# chalupa_v3.net
KiCad netlist of a schematic drawn in EAGLE
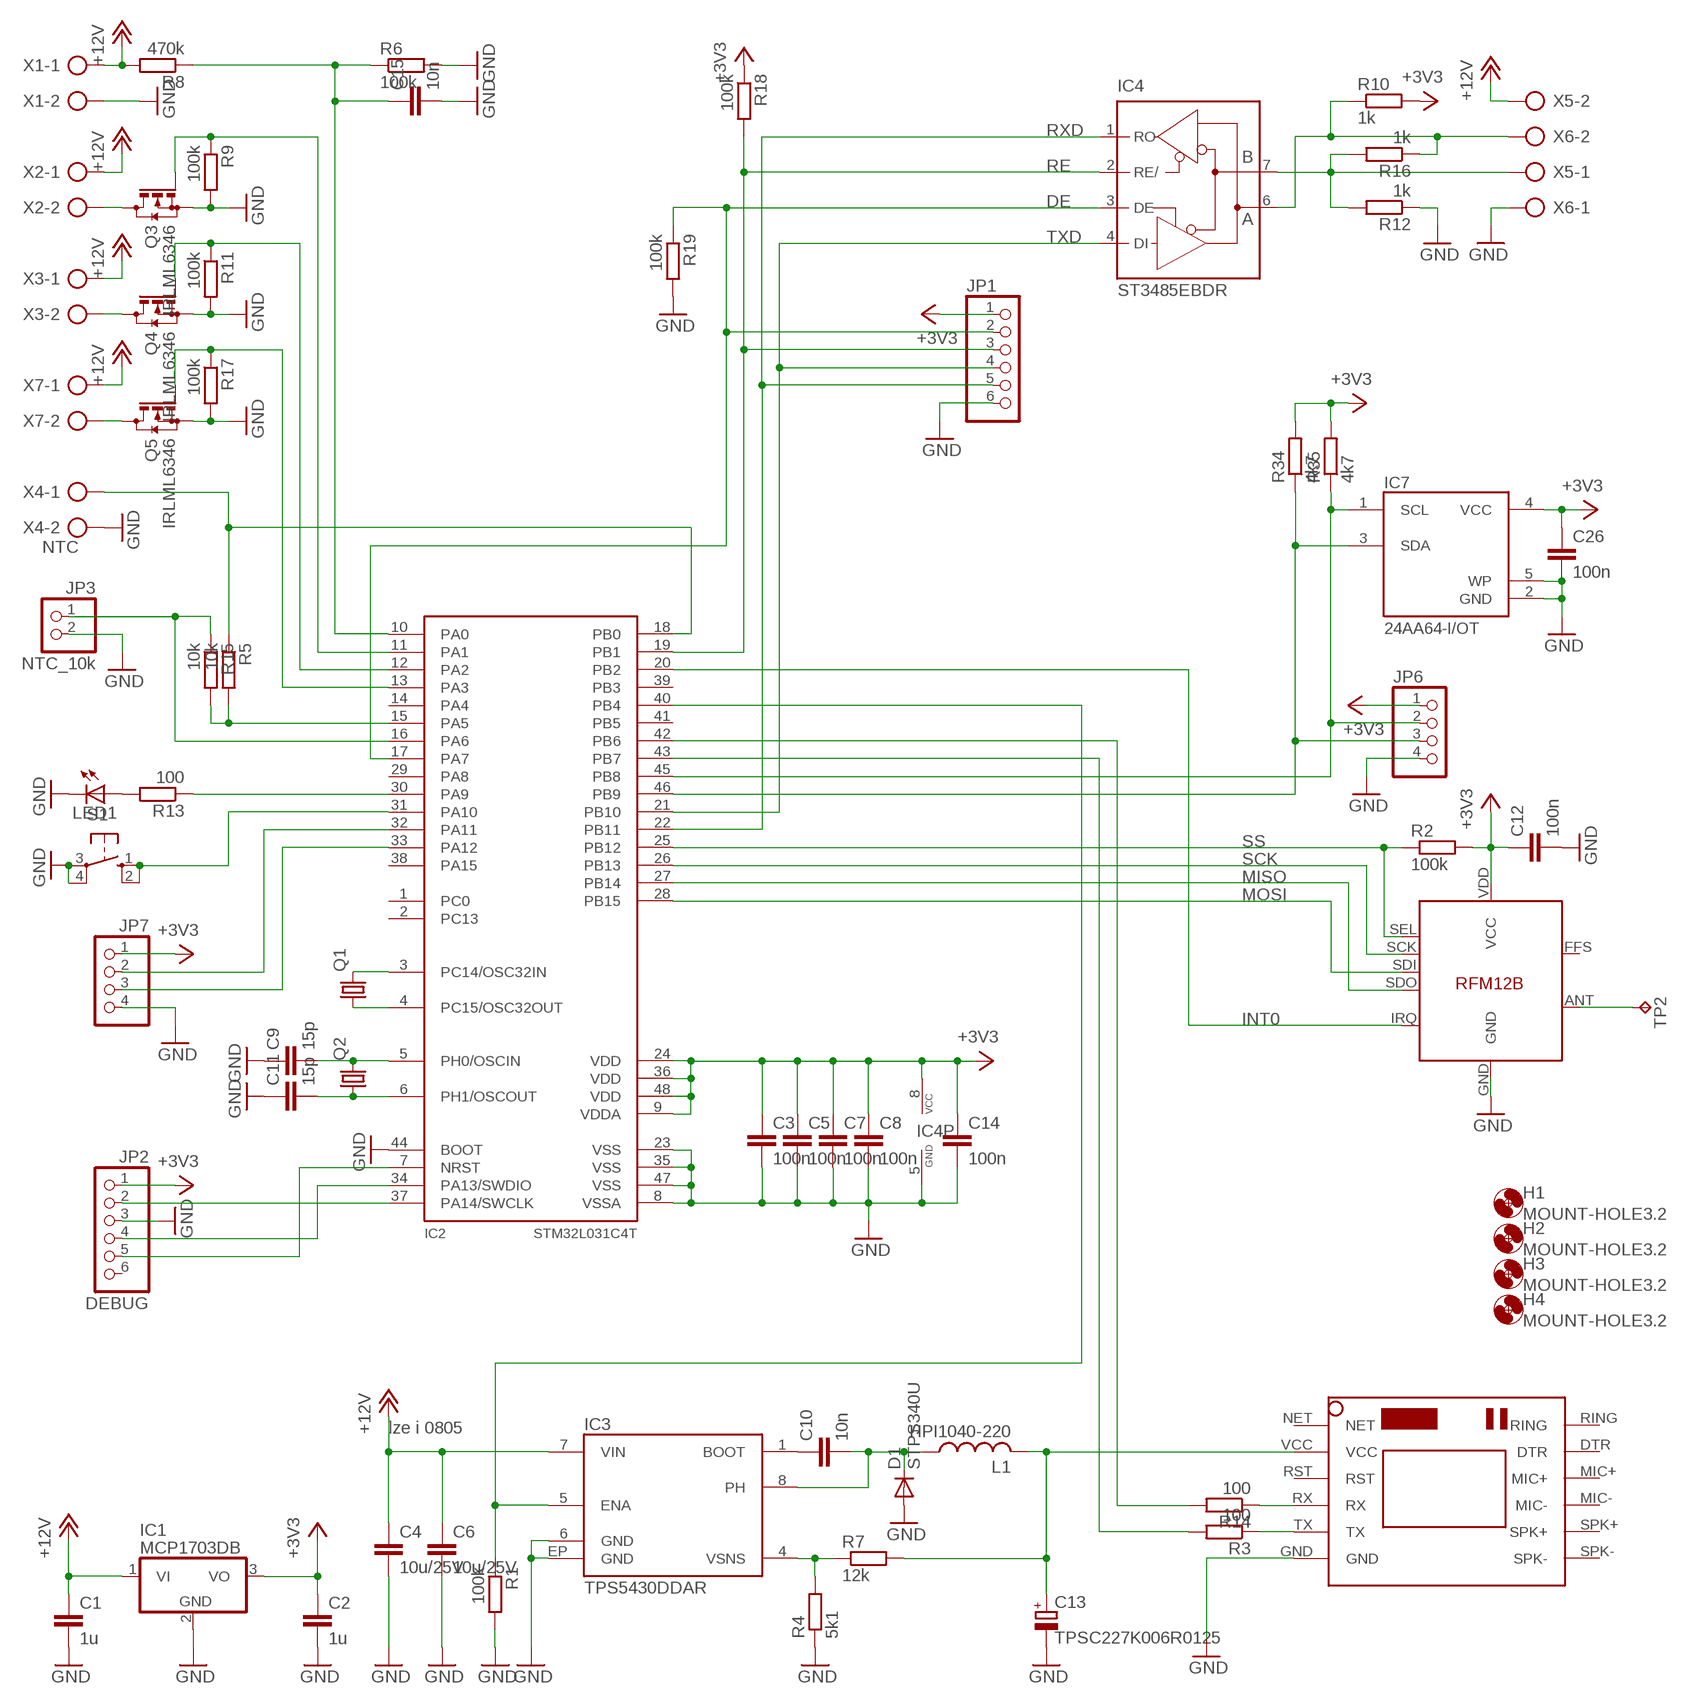
[diagram p0: schematic, sheet 1]

(export (version "E")
  (design (tool "Eeschema 10.0.6"))
  (components
    (comp (ref "C1")
      (value "1u")
      (footprint "eagle-import:C0603")
      (libsource (lib "eagle-import") (part "C-EUC0603"))
    )
    (comp (ref "C2")
      (value "1u")
      (footprint "eagle-import:C0603")
      (libsource (lib "eagle-import") (part "C-EUC0603"))
    )
    (comp (ref "C3")
      (value "100n")
      (footprint "eagle-import:C0603")
      (libsource (lib "eagle-import") (part "C-EUC0603"))
    )
    (comp (ref "C4")
      (value "10u/25V")
      (footprint "eagle-import:C1206")
      (libsource (lib "eagle-import") (part "C-EUC1206"))
    )
    (comp (ref "C5")
      (value "100n")
      (footprint "eagle-import:C0603")
      (libsource (lib "eagle-import") (part "C-EUC0603"))
    )
    (comp (ref "C6")
      (value "10u/25V")
      (footprint "eagle-import:C1206")
      (libsource (lib "eagle-import") (part "C-EUC1206"))
    )
    (comp (ref "C7")
      (value "100n")
      (footprint "eagle-import:C0603")
      (libsource (lib "eagle-import") (part "C-EUC0603"))
    )
    (comp (ref "C8")
      (value "100n")
      (footprint "eagle-import:C0603")
      (libsource (lib "eagle-import") (part "C-EUC0603"))
    )
    (comp (ref "C9")
      (value "15p")
      (footprint "eagle-import:C0603")
      (libsource (lib "eagle-import") (part "C-EUC0603"))
    )
    (comp (ref "C10")
      (value "10n")
      (footprint "eagle-import:C0603")
      (libsource (lib "eagle-import") (part "C-EUC0603"))
    )
    (comp (ref "C11")
      (value "15p")
      (footprint "eagle-import:C0603")
      (libsource (lib "eagle-import") (part "C-EUC0603"))
    )
    (comp (ref "C12")
      (value "100n")
      (footprint "eagle-import:C0603")
      (libsource (lib "eagle-import") (part "C-EUC0603"))
    )
    (comp (ref "C13")
      (value "TPSC227K006R0125")
      (footprint "eagle-import:SMC_C")
      (libsource (lib "eagle-import") (part "CPOL-EUSMCC"))
    )
    (comp (ref "C14")
      (value "100n")
      (footprint "eagle-import:C0603")
      (libsource (lib "eagle-import") (part "C-EUC0603"))
    )
    (comp (ref "C15")
      (value "10n")
      (footprint "eagle-import:C0603")
      (libsource (lib "eagle-import") (part "C-EUC0603"))
    )
    (comp (ref "C26")
      (value "100n")
      (footprint "eagle-import:C0603")
      (libsource (lib "eagle-import") (part "C-EUC0603"))
    )
    (comp (ref "D1")
      (value "STPS340U")
      (footprint "eagle-import:SMB")
      (libsource (lib "eagle-import") (part "DIODE-SMB"))
    )
    (comp (ref "H1")
      (value "MOUNT-HOLE3.2")
      (footprint "eagle-import:3,2")
      (libsource (lib "eagle-import") (part "MOUNT-HOLE3.2"))
    )
    (comp (ref "H2")
      (value "MOUNT-HOLE3.2")
      (footprint "eagle-import:3,2")
      (libsource (lib "eagle-import") (part "MOUNT-HOLE3.2"))
    )
    (comp (ref "H3")
      (value "MOUNT-HOLE3.2")
      (footprint "eagle-import:3,2")
      (libsource (lib "eagle-import") (part "MOUNT-HOLE3.2"))
    )
    (comp (ref "H4")
      (value "MOUNT-HOLE3.2")
      (footprint "eagle-import:3,2")
      (libsource (lib "eagle-import") (part "MOUNT-HOLE3.2"))
    )
    (comp (ref "IC1")
      (value "MCP1703DB")
      (footprint "eagle-import:SOT223")
      (libsource (lib "eagle-import") (part "MCP1703DB"))
    )
    (comp (ref "IC2")
      (value "STM32L031C4T")
      (footprint "eagle-import:LQFP48")
      (libsource (lib "eagle-import") (part "STM32L031C4T"))
    )
    (comp (ref "IC3")
      (value "TPS5430DDAR")
      (footprint "eagle-import:DDA")
      (libsource (lib "eagle-import") (part "TPS5430DDA"))
    )
    (comp (ref "IC4")
      (value "ST3485EBDR")
      (footprint "eagle-import:SO08")
      (fields (field (name "MF") "MAXIM") (field (name "MPN") "MAX481CSA"))
      (libsource (lib "eagle-import") (part "MAX481CSA"))
    )
    (comp (ref "IC5")
      (value "SIM800LMODULE")
      (footprint "eagle-import:SIM800LMODULE")
      (libsource (lib "eagle-import") (part "SIM800LMODULE"))
    )
    (comp (ref "IC7")
      (value "24AA64-I/OT")
      (footprint "eagle-import:SOT23-5")
      (libsource (lib "eagle-import") (part "24AA64-I/OT"))
    )
    (comp (ref "JP1")
      (value "PINHD-1X6")
      (footprint "eagle-import:1X06")
      (libsource (lib "eagle-import") (part "PINHD-1X6"))
    )
    (comp (ref "JP2")
      (value "DEBUG")
      (footprint "eagle-import:1X06")
      (libsource (lib "eagle-import") (part "PINHD-1X6"))
    )
    (comp (ref "JP3")
      (value "NTC_10k")
      (footprint "eagle-import:1X02")
      (libsource (lib "eagle-import") (part "PINHD-1X2"))
    )
    (comp (ref "JP6")
      (value "PINHD-1X4")
      (footprint "eagle-import:1X04")
      (libsource (lib "eagle-import") (part "PINHD-1X4"))
    )
    (comp (ref "JP7")
      (value "PINHD-1X4")
      (footprint "eagle-import:1X04")
      (libsource (lib "eagle-import") (part "PINHD-1X4"))
    )
    (comp (ref "L1")
      (value "HPI1040-220")
      (footprint "eagle-import:HPI1040")
      (libsource (lib "eagle-import") (part "L-USHPI1040"))
    )
    (comp (ref "LED1")
      (value "LEDCHIP-LED0805")
      (footprint "eagle-import:CHIP-LED0805")
      (libsource (lib "eagle-import") (part "LEDCHIP-LED0805"))
    )
    (comp (ref "Q1")
      (value "CRYSTALTC38H")
      (footprint "eagle-import:TC38H")
      (libsource (lib "eagle-import") (part "CRYSTALTC38H"))
    )
    (comp (ref "Q2")
      (value "CRYSTALHC49UP")
      (footprint "eagle-import:HC49UP")
      (libsource (lib "eagle-import") (part "CRYSTALHC49UP"))
    )
    (comp (ref "Q3")
      (value "IRLML6346")
      (footprint "eagle-import:SOT23")
      (libsource (lib "eagle-import") (part "BSS123"))
    )
    (comp (ref "Q4")
      (value "IRLML6346")
      (footprint "eagle-import:SOT23")
      (libsource (lib "eagle-import") (part "BSS123"))
    )
    (comp (ref "Q5")
      (value "IRLML6346")
      (footprint "eagle-import:SOT23")
      (libsource (lib "eagle-import") (part "BSS123"))
    )
    (comp (ref "R1")
      (value "100k")
      (footprint "eagle-import:R0603")
      (libsource (lib "eagle-import") (part "R-EU_R0603"))
    )
    (comp (ref "R2")
      (value "100k")
      (footprint "eagle-import:R0603")
      (libsource (lib "eagle-import") (part "R-EU_R0603"))
    )
    (comp (ref "R3")
      (value "100")
      (footprint "eagle-import:R0603")
      (libsource (lib "eagle-import") (part "R-EU_R0603"))
    )
    (comp (ref "R4")
      (value "5k1")
      (footprint "eagle-import:R0603")
      (libsource (lib "eagle-import") (part "R-EU_R0603"))
    )
    (comp (ref "R5")
      (value "10k")
      (footprint "eagle-import:R0603")
      (libsource (lib "eagle-import") (part "R-EU_R0603"))
    )
    (comp (ref "R6")
      (value "100k")
      (footprint "eagle-import:R0603")
      (libsource (lib "eagle-import") (part "R-EU_R0603"))
    )
    (comp (ref "R7")
      (value "12k")
      (footprint "eagle-import:R0603")
      (libsource (lib "eagle-import") (part "R-EU_R0603"))
    )
    (comp (ref "R8")
      (value "470k")
      (footprint "eagle-import:R0603")
      (libsource (lib "eagle-import") (part "R-EU_R0603"))
    )
    (comp (ref "R9")
      (value "100k")
      (footprint "eagle-import:R0603")
      (libsource (lib "eagle-import") (part "R-EU_R0603"))
    )
    (comp (ref "R10")
      (value "1k")
      (footprint "eagle-import:R0603")
      (libsource (lib "eagle-import") (part "R-EU_R0603"))
    )
    (comp (ref "R11")
      (value "100k")
      (footprint "eagle-import:R0603")
      (libsource (lib "eagle-import") (part "R-EU_R0603"))
    )
    (comp (ref "R12")
      (value "1k")
      (footprint "eagle-import:R0603")
      (libsource (lib "eagle-import") (part "R-EU_R0603"))
    )
    (comp (ref "R13")
      (value "100")
      (footprint "eagle-import:R0603")
      (libsource (lib "eagle-import") (part "R-EU_R0603"))
    )
    (comp (ref "R14")
      (value "100")
      (footprint "eagle-import:R0603")
      (libsource (lib "eagle-import") (part "R-EU_R0603"))
    )
    (comp (ref "R15")
      (value "10k")
      (footprint "eagle-import:R0603")
      (libsource (lib "eagle-import") (part "R-EU_R0603"))
    )
    (comp (ref "R16")
      (value "1k")
      (footprint "eagle-import:R0603")
      (libsource (lib "eagle-import") (part "R-EU_R0603"))
    )
    (comp (ref "R17")
      (value "100k")
      (footprint "eagle-import:R0603")
      (libsource (lib "eagle-import") (part "R-EU_R0603"))
    )
    (comp (ref "R18")
      (value "100k")
      (footprint "eagle-import:R0603")
      (libsource (lib "eagle-import") (part "R-EU_R0603"))
    )
    (comp (ref "R19")
      (value "100k")
      (footprint "eagle-import:R0603")
      (libsource (lib "eagle-import") (part "R-EU_R0603"))
    )
    (comp (ref "R34")
      (value "4k7")
      (footprint "eagle-import:R0603")
      (libsource (lib "eagle-import") (part "R-EU_R0603"))
    )
    (comp (ref "R35")
      (value "4k7")
      (footprint "eagle-import:R0603")
      (libsource (lib "eagle-import") (part "R-EU_R0603"))
    )
    (comp (ref "RFM12B")
      (value "RFM12B")
      (footprint "eagle-import:RFM12B")
      (libsource (lib "eagle-import") (part "RFM12B"))
    )
    (comp (ref "S1")
      (value "10-XX")
      (footprint "eagle-import:B3F-10XX")
      (fields (field (name "MPN") "B3F-1000"))
      (libsource (lib "eagle-import") (part "10-XX"))
    )
    (comp (ref "TP2")
      (value "ANT868")
      (footprint "eagle-import:B2,54")
      (libsource (lib "eagle-import") (part "TPB2,54"))
    )
    (comp (ref "X1")
      (value "AK500/2")
      (footprint "eagle-import:AK500_2")
      (libsource (lib "eagle-import") (part "AK500/2"))
    )
    (comp (ref "X2")
      (value "AK500/2")
      (footprint "eagle-import:AK500_2")
      (libsource (lib "eagle-import") (part "AK500/2"))
    )
    (comp (ref "X3")
      (value "AK500/2")
      (footprint "eagle-import:AK500_2")
      (libsource (lib "eagle-import") (part "AK500/2"))
    )
    (comp (ref "X4")
      (value "NTC")
      (footprint "eagle-import:AK500_2")
      (libsource (lib "eagle-import") (part "AK500/2"))
    )
    (comp (ref "X5")
      (value "AK500/2")
      (footprint "eagle-import:AK500_2")
      (libsource (lib "eagle-import") (part "AK500/2"))
    )
    (comp (ref "X6")
      (value "AK500/2")
      (footprint "eagle-import:AK500_2")
      (libsource (lib "eagle-import") (part "AK500/2"))
    )
    (comp (ref "X7")
      (value "AK500/2")
      (footprint "eagle-import:AK500_2")
      (libsource (lib "eagle-import") (part "AK500/2"))
    )
  )
  (nets
    (net (code "1") (name "+3V3") (class "Default")
      (node (ref "C12") (pin "1") (pinfunction "1_1") (pintype "passive"))
      (node (ref "C14") (pin "1") (pinfunction "1_1") (pintype "passive"))
      (node (ref "C2") (pin "1") (pinfunction "1_1") (pintype "passive"))
      (node (ref "C26") (pin "1") (pinfunction "1_1") (pintype "passive"))
      (node (ref "C3") (pin "1") (pinfunction "1_1") (pintype "passive"))
      (node (ref "C5") (pin "1") (pinfunction "1_1") (pintype "passive"))
      (node (ref "C7") (pin "1") (pinfunction "1_1") (pintype "passive"))
      (node (ref "C8") (pin "1") (pinfunction "1_1") (pintype "passive"))
      (node (ref "IC1") (pin "3") (pinfunction "VO_3") (pintype "passive"))
      (node (ref "IC2") (pin "24") (pinfunction "VDD_24") (pintype "power_in"))
      (node (ref "IC2") (pin "36") (pinfunction "VDD_36") (pintype "power_in"))
      (node (ref "IC2") (pin "48") (pinfunction "VDD_48") (pintype "power_in"))
      (node (ref "IC2") (pin "9") (pinfunction "VDDA_9") (pintype "power_in"))
      (node (ref "IC4") (pin "8") (pinfunction "VCC_8") (pintype "power_in"))
      (node (ref "IC7") (pin "4") (pinfunction "VCC_4") (pintype "power_in"))
      (node (ref "JP1") (pin "1") (pinfunction "1_1") (pintype "passive"))
      (node (ref "JP2") (pin "1") (pinfunction "1_1") (pintype "passive"))
      (node (ref "JP6") (pin "1") (pinfunction "1_1") (pintype "passive"))
      (node (ref "JP7") (pin "1") (pinfunction "1_1") (pintype "passive"))
      (node (ref "R10") (pin "2") (pinfunction "2_2") (pintype "passive"))
      (node (ref "R18") (pin "1") (pinfunction "1_1") (pintype "passive"))
      (node (ref "R2") (pin "2") (pinfunction "2_2") (pintype "passive"))
      (node (ref "R34") (pin "2") (pinfunction "2_2") (pintype "passive"))
      (node (ref "R35") (pin "2") (pinfunction "2_2") (pintype "passive"))
      (node (ref "RFM12B") (pin "VDD") (pinfunction "VCC_VDD") (pintype "power_in"))
    )
    (net (code "2") (name "+12V") (class "Default")
      (node (ref "C1") (pin "1") (pinfunction "1_1") (pintype "passive"))
      (node (ref "C4") (pin "1") (pinfunction "1_1") (pintype "passive"))
      (node (ref "C6") (pin "1") (pinfunction "1_1") (pintype "passive"))
      (node (ref "IC1") (pin "1") (pinfunction "VI_1") (pintype "input"))
      (node (ref "IC3") (pin "7") (pinfunction "VIN_7") (pintype "power_in"))
      (node (ref "R8") (pin "2") (pinfunction "2_2") (pintype "passive"))
      (node (ref "X1") (pin "1") (pinfunction "KL_1") (pintype "passive"))
      (node (ref "X2") (pin "1") (pinfunction "KL_1") (pintype "passive"))
      (node (ref "X3") (pin "1") (pinfunction "KL_1") (pintype "passive"))
      (node (ref "X5") (pin "2") (pinfunction "KL_2") (pintype "passive"))
      (node (ref "X7") (pin "1") (pinfunction "KL_1") (pintype "passive"))
    )
    (net (code "3") (name "/DE") (class "Default")
      (node (ref "IC2") (pin "17") (pinfunction "PA7_17") (pintype "bidirectional"))
      (node (ref "IC4") (pin "3") (pinfunction "DE_3") (pintype "input"))
      (node (ref "JP1") (pin "2") (pinfunction "2_2") (pintype "passive"))
      (node (ref "R19") (pin "1") (pinfunction "1_1") (pintype "passive"))
    )
    (net (code "4") (name "/INT0") (class "Default")
      (node (ref "IC2") (pin "20") (pinfunction "PB2_20") (pintype "bidirectional"))
      (node (ref "RFM12B") (pin "IRQ") (pinfunction "IRQ_IRQ") (pintype "open_collector"))
    )
    (net (code "5") (name "/MISO") (class "Default")
      (node (ref "IC2") (pin "27") (pinfunction "PB14_27") (pintype "bidirectional"))
      (node (ref "RFM12B") (pin "SDO") (pinfunction "SDO_SDO") (pintype "output"))
    )
    (net (code "6") (name "/MOSI") (class "Default")
      (node (ref "IC2") (pin "28") (pinfunction "PB15_28") (pintype "bidirectional"))
      (node (ref "RFM12B") (pin "SDI") (pinfunction "SDI_SDI") (pintype "input"))
    )
    (net (code "7") (name "/RE") (class "Default")
      (node (ref "IC2") (pin "19") (pinfunction "PB1_19") (pintype "bidirectional"))
      (node (ref "IC4") (pin "2") (pinfunction "RE/_2") (pintype "input"))
      (node (ref "JP1") (pin "3") (pinfunction "3_3") (pintype "passive"))
      (node (ref "R18") (pin "2") (pinfunction "2_2") (pintype "passive"))
    )
    (net (code "8") (name "/RXD") (class "Default")
      (node (ref "IC2") (pin "22") (pinfunction "PB11_22") (pintype "bidirectional"))
      (node (ref "IC4") (pin "1") (pinfunction "RO_1") (pintype "output"))
      (node (ref "JP1") (pin "5") (pinfunction "5_5") (pintype "passive"))
    )
    (net (code "9") (name "/SCK") (class "Default")
      (node (ref "IC2") (pin "26") (pinfunction "PB13_26") (pintype "bidirectional"))
      (node (ref "RFM12B") (pin "SCK") (pinfunction "SCK_SCK") (pintype "input"))
    )
    (net (code "10") (name "/SS") (class "Default")
      (node (ref "IC2") (pin "25") (pinfunction "PB12_25") (pintype "bidirectional"))
      (node (ref "R2") (pin "1") (pinfunction "1_1") (pintype "passive"))
      (node (ref "RFM12B") (pin "SEL") (pinfunction "SEL_SEL") (pintype "input"))
    )
    (net (code "11") (name "/TXD") (class "Default")
      (node (ref "IC2") (pin "21") (pinfunction "PB10_21") (pintype "bidirectional"))
      (node (ref "IC4") (pin "4") (pinfunction "DI_4") (pintype "input"))
      (node (ref "JP1") (pin "4") (pinfunction "4_4") (pintype "passive"))
    )
    (net (code "12") (name "GND") (class "Default")
      (node (ref "C1") (pin "2") (pinfunction "2_2") (pintype "passive"))
      (node (ref "C11") (pin "1") (pinfunction "1_1") (pintype "passive"))
      (node (ref "C12") (pin "2") (pinfunction "2_2") (pintype "passive"))
      (node (ref "C13") (pin "-") (pinfunction "-_-") (pintype "passive"))
      (node (ref "C14") (pin "2") (pinfunction "2_2") (pintype "passive"))
      (node (ref "C15") (pin "2") (pinfunction "2_2") (pintype "passive"))
      (node (ref "C2") (pin "2") (pinfunction "2_2") (pintype "passive"))
      (node (ref "C26") (pin "2") (pinfunction "2_2") (pintype "passive"))
      (node (ref "C3") (pin "2") (pinfunction "2_2") (pintype "passive"))
      (node (ref "C4") (pin "2") (pinfunction "2_2") (pintype "passive"))
      (node (ref "C5") (pin "2") (pinfunction "2_2") (pintype "passive"))
      (node (ref "C6") (pin "2") (pinfunction "2_2") (pintype "passive"))
      (node (ref "C7") (pin "2") (pinfunction "2_2") (pintype "passive"))
      (node (ref "C8") (pin "2") (pinfunction "2_2") (pintype "passive"))
      (node (ref "C9") (pin "1") (pinfunction "1_1") (pintype "passive"))
      (node (ref "D1") (pin "A") (pinfunction "A_A") (pintype "passive"))
      (node (ref "IC1") (pin "2") (pinfunction "GND_2") (pintype "passive"))
      (node (ref "IC2") (pin "23") (pinfunction "VSS_23") (pintype "power_in"))
      (node (ref "IC2") (pin "35") (pinfunction "VSS_35") (pintype "power_in"))
      (node (ref "IC2") (pin "44") (pinfunction "BOOT_44") (pintype "bidirectional"))
      (node (ref "IC2") (pin "47") (pinfunction "VSS_47") (pintype "power_in"))
      (node (ref "IC2") (pin "8") (pinfunction "VSSA_8") (pintype "power_in"))
      (node (ref "IC3") (pin "6") (pinfunction "GND_6") (pintype "power_in"))
      (node (ref "IC3") (pin "EP") (pinfunction "GND_EP") (pintype "power_in"))
      (node (ref "IC4") (pin "5") (pinfunction "GND_5") (pintype "power_in"))
      (node (ref "IC5") (pin "GND") (pinfunction "GND_GND") (pintype "bidirectional"))
      (node (ref "IC7") (pin "2") (pinfunction "GND_2") (pintype "power_in"))
      (node (ref "IC7") (pin "5") (pinfunction "WP_5") (pintype "input"))
      (node (ref "JP1") (pin "6") (pinfunction "6_6") (pintype "passive"))
      (node (ref "JP2") (pin "3") (pinfunction "3_3") (pintype "passive"))
      (node (ref "JP3") (pin "2") (pinfunction "2_2") (pintype "passive"))
      (node (ref "JP6") (pin "4") (pinfunction "4_4") (pintype "passive"))
      (node (ref "JP7") (pin "4") (pinfunction "4_4") (pintype "passive"))
      (node (ref "LED1") (pin "C") (pinfunction "C_C") (pintype "passive"))
      (node (ref "Q3") (pin "2") (pinfunction "S_2") (pintype "passive"))
      (node (ref "Q4") (pin "2") (pinfunction "S_2") (pintype "passive"))
      (node (ref "Q5") (pin "2") (pinfunction "S_2") (pintype "passive"))
      (node (ref "R1") (pin "2") (pinfunction "2_2") (pintype "passive"))
      (node (ref "R11") (pin "2") (pinfunction "2_2") (pintype "passive"))
      (node (ref "R12") (pin "1") (pinfunction "1_1") (pintype "passive"))
      (node (ref "R17") (pin "2") (pinfunction "2_2") (pintype "passive"))
      (node (ref "R19") (pin "2") (pinfunction "2_2") (pintype "passive"))
      (node (ref "R4") (pin "1") (pinfunction "1_1") (pintype "passive"))
      (node (ref "R6") (pin "2") (pinfunction "2_2") (pintype "passive"))
      (node (ref "R9") (pin "2") (pinfunction "2_2") (pintype "passive"))
      (node (ref "RFM12B") (pin "GND") (pinfunction "GND_GND") (pintype "power_in"))
      (node (ref "S1") (pin "3") (pinfunction "P_3") (pintype "passive"))
      (node (ref "S1") (pin "4") (pinfunction "P1_4") (pintype "passive"))
      (node (ref "X1") (pin "2") (pinfunction "KL_2") (pintype "passive"))
      (node (ref "X4") (pin "2") (pinfunction "KL_2") (pintype "passive"))
      (node (ref "X6") (pin "1") (pinfunction "KL_1") (pintype "passive"))
    )
    (net (code "13") (name "Net-(C13-Pad+)") (class "Default")
      (node (ref "C13") (pin "+") (pinfunction "+_+") (pintype "passive"))
      (node (ref "IC5") (pin "VCC") (pinfunction "VCC_VCC") (pintype "bidirectional"))
      (node (ref "L1") (pin "2") (pinfunction "2_2") (pintype "passive"))
      (node (ref "R7") (pin "2") (pinfunction "2_2") (pintype "passive"))
    )
    (net (code "14") (name "Net-(IC2-NRST)") (class "Default")
      (node (ref "IC2") (pin "7") (pinfunction "NRST_7") (pintype "bidirectional"))
      (node (ref "JP2") (pin "5") (pinfunction "5_5") (pintype "passive"))
    )
    (net (code "15") (name "Net-(IC2-PA0)") (class "Default")
      (node (ref "C15") (pin "1") (pinfunction "1_1") (pintype "passive"))
      (node (ref "IC2") (pin "10") (pinfunction "PA0_10") (pintype "bidirectional"))
      (node (ref "R6") (pin "1") (pinfunction "1_1") (pintype "passive"))
      (node (ref "R8") (pin "1") (pinfunction "1_1") (pintype "passive"))
    )
    (net (code "16") (name "Net-(IC2-PA1)") (class "Default")
      (node (ref "IC2") (pin "11") (pinfunction "PA1_11") (pintype "bidirectional"))
      (node (ref "Q3") (pin "1") (pinfunction "G_1") (pintype "passive"))
      (node (ref "R9") (pin "1") (pinfunction "1_1") (pintype "passive"))
    )
    (net (code "17") (name "Net-(IC2-PA2)") (class "Default")
      (node (ref "IC2") (pin "12") (pinfunction "PA2_12") (pintype "bidirectional"))
      (node (ref "Q4") (pin "1") (pinfunction "G_1") (pintype "passive"))
      (node (ref "R11") (pin "1") (pinfunction "1_1") (pintype "passive"))
    )
    (net (code "18") (name "Net-(IC2-PA3)") (class "Default")
      (node (ref "IC2") (pin "13") (pinfunction "PA3_13") (pintype "bidirectional"))
      (node (ref "Q5") (pin "1") (pinfunction "G_1") (pintype "passive"))
      (node (ref "R17") (pin "1") (pinfunction "1_1") (pintype "passive"))
    )
    (net (code "19") (name "Net-(IC2-PA5)") (class "Default")
      (node (ref "IC2") (pin "15") (pinfunction "PA5_15") (pintype "bidirectional"))
      (node (ref "R15") (pin "2") (pinfunction "2_2") (pintype "passive"))
      (node (ref "R5") (pin "2") (pinfunction "2_2") (pintype "passive"))
    )
    (net (code "20") (name "Net-(IC2-PA6)") (class "Default")
      (node (ref "IC2") (pin "16") (pinfunction "PA6_16") (pintype "bidirectional"))
      (node (ref "JP3") (pin "1") (pinfunction "1_1") (pintype "passive"))
      (node (ref "R15") (pin "1") (pinfunction "1_1") (pintype "passive"))
    )
    (net (code "21") (name "Net-(IC2-PA9)") (class "Default")
      (node (ref "IC2") (pin "30") (pinfunction "PA9_30") (pintype "bidirectional"))
      (node (ref "R13") (pin "1") (pinfunction "1_1") (pintype "passive"))
    )
    (net (code "22") (name "Net-(IC2-PA10)") (class "Default")
      (node (ref "IC2") (pin "31") (pinfunction "PA10_31") (pintype "bidirectional"))
      (node (ref "S1") (pin "1") (pinfunction "S_1") (pintype "passive"))
      (node (ref "S1") (pin "2") (pinfunction "S1_2") (pintype "passive"))
    )
    (net (code "23") (name "Net-(IC2-PA11)") (class "Default")
      (node (ref "IC2") (pin "32") (pinfunction "PA11_32") (pintype "bidirectional"))
      (node (ref "JP7") (pin "2") (pinfunction "2_2") (pintype "passive"))
    )
    (net (code "24") (name "Net-(IC2-PA12)") (class "Default")
      (node (ref "IC2") (pin "33") (pinfunction "PA12_33") (pintype "bidirectional"))
      (node (ref "JP7") (pin "3") (pinfunction "3_3") (pintype "passive"))
    )
    (net (code "25") (name "Net-(IC2-PA13{slash}SWDIO)") (class "Default")
      (node (ref "IC2") (pin "34") (pinfunction "PA13/SWDIO_34") (pintype "bidirectional"))
      (node (ref "JP2") (pin "4") (pinfunction "4_4") (pintype "passive"))
    )
    (net (code "26") (name "Net-(IC2-PA14{slash}SWCLK)") (class "Default")
      (node (ref "IC2") (pin "37") (pinfunction "PA14/SWCLK_37") (pintype "bidirectional"))
      (node (ref "JP2") (pin "2") (pinfunction "2_2") (pintype "passive"))
    )
    (net (code "27") (name "Net-(IC2-PB0)") (class "Default")
      (node (ref "IC2") (pin "18") (pinfunction "PB0_18") (pintype "bidirectional"))
      (node (ref "R5") (pin "1") (pinfunction "1_1") (pintype "passive"))
      (node (ref "X4") (pin "1") (pinfunction "KL_1") (pintype "passive"))
    )
    (net (code "28") (name "Net-(IC2-PB4)") (class "Default")
      (node (ref "IC2") (pin "40") (pinfunction "PB4_40") (pintype "bidirectional"))
      (node (ref "IC3") (pin "5") (pinfunction "ENA_5") (pintype "bidirectional"))
      (node (ref "R1") (pin "1") (pinfunction "1_1") (pintype "passive"))
    )
    (net (code "29") (name "Net-(IC2-PB6)") (class "Default")
      (node (ref "IC2") (pin "42") (pinfunction "PB6_42") (pintype "bidirectional"))
      (node (ref "R14") (pin "2") (pinfunction "2_2") (pintype "passive"))
    )
    (net (code "30") (name "Net-(IC2-PB7)") (class "Default")
      (node (ref "IC2") (pin "43") (pinfunction "PB7_43") (pintype "bidirectional"))
      (node (ref "R3") (pin "2") (pinfunction "2_2") (pintype "passive"))
    )
    (net (code "31") (name "Net-(IC2-PB8)") (class "Default")
      (node (ref "IC2") (pin "45") (pinfunction "PB8_45") (pintype "bidirectional"))
      (node (ref "IC7") (pin "1") (pinfunction "SCL_1") (pintype "input"))
      (node (ref "JP6") (pin "2") (pinfunction "2_2") (pintype "passive"))
      (node (ref "R35") (pin "1") (pinfunction "1_1") (pintype "passive"))
    )
    (net (code "32") (name "Net-(IC2-PB9)") (class "Default")
      (node (ref "IC2") (pin "46") (pinfunction "PB9_46") (pintype "bidirectional"))
      (node (ref "IC7") (pin "3") (pinfunction "SDA_3") (pintype "bidirectional"))
      (node (ref "JP6") (pin "3") (pinfunction "3_3") (pintype "passive"))
      (node (ref "R34") (pin "1") (pinfunction "1_1") (pintype "passive"))
    )
    (net (code "33") (name "Net-(IC2-PC14{slash}OSC32IN)") (class "Default")
      (node (ref "IC2") (pin "3") (pinfunction "PC14/OSC32IN_3") (pintype "passive"))
      (node (ref "Q1") (pin "2") (pinfunction "2_2") (pintype "passive"))
    )
    (net (code "34") (name "Net-(IC2-PC15{slash}OSC32OUT)") (class "Default")
      (node (ref "IC2") (pin "4") (pinfunction "PC15/OSC32OUT_4") (pintype "passive"))
      (node (ref "Q1") (pin "1") (pinfunction "1_1") (pintype "passive"))
    )
    (net (code "35") (name "Net-(IC2-PH0{slash}OSCIN)") (class "Default")
      (node (ref "C9") (pin "2") (pinfunction "2_2") (pintype "passive"))
      (node (ref "IC2") (pin "5") (pinfunction "PH0/OSCIN_5") (pintype "passive"))
      (node (ref "Q2") (pin "2") (pinfunction "2_2") (pintype "passive"))
    )
    (net (code "36") (name "Net-(IC2-PH1{slash}OSCOUT)") (class "Default")
      (node (ref "C11") (pin "2") (pinfunction "2_2") (pintype "passive"))
      (node (ref "IC2") (pin "6") (pinfunction "PH1/OSCOUT_6") (pintype "passive"))
      (node (ref "Q2") (pin "1") (pinfunction "1_1") (pintype "passive"))
    )
    (net (code "37") (name "Net-(IC3-BOOT)") (class "Default")
      (node (ref "C10") (pin "1") (pinfunction "1_1") (pintype "passive"))
      (node (ref "IC3") (pin "1") (pinfunction "BOOT_1") (pintype "passive"))
    )
    (net (code "38") (name "Net-(IC3-PH)") (class "Default")
      (node (ref "C10") (pin "2") (pinfunction "2_2") (pintype "passive"))
      (node (ref "D1") (pin "C") (pinfunction "C_C") (pintype "passive"))
      (node (ref "IC3") (pin "8") (pinfunction "PH_8") (pintype "passive"))
      (node (ref "L1") (pin "1") (pinfunction "1_1") (pintype "passive"))
    )
    (net (code "39") (name "Net-(IC3-VSNS)") (class "Default")
      (node (ref "IC3") (pin "4") (pinfunction "VSNS_4") (pintype "input"))
      (node (ref "R4") (pin "2") (pinfunction "2_2") (pintype "passive"))
      (node (ref "R7") (pin "1") (pinfunction "1_1") (pintype "passive"))
    )
    (net (code "40") (name "Net-(IC4A-A)") (class "Default")
      (node (ref "IC4") (pin "6") (pinfunction "A_6") (pintype "passive"))
      (node (ref "R10") (pin "1") (pinfunction "1_1") (pintype "passive"))
      (node (ref "R16") (pin "1") (pinfunction "1_1") (pintype "passive"))
      (node (ref "X6") (pin "2") (pinfunction "KL_2") (pintype "passive"))
    )
    (net (code "41") (name "Net-(IC4A-B)") (class "Default")
      (node (ref "IC4") (pin "7") (pinfunction "B_7") (pintype "passive"))
      (node (ref "R12") (pin "2") (pinfunction "2_2") (pintype "passive"))
      (node (ref "R16") (pin "2") (pinfunction "2_2") (pintype "passive"))
      (node (ref "X5") (pin "1") (pinfunction "KL_1") (pintype "passive"))
    )
    (net (code "42") (name "Net-(IC5-PadRX)") (class "Default")
      (node (ref "IC5") (pin "RX") (pinfunction "RX_RX") (pintype "bidirectional"))
      (node (ref "R14") (pin "1") (pinfunction "1_1") (pintype "passive"))
    )
    (net (code "43") (name "Net-(IC5-PadTX)") (class "Default")
      (node (ref "IC5") (pin "TX") (pinfunction "TX_TX") (pintype "bidirectional"))
      (node (ref "R3") (pin "1") (pinfunction "1_1") (pintype "passive"))
    )
    (net (code "44") (name "Net-(LED1-PadA)") (class "Default")
      (node (ref "LED1") (pin "A") (pinfunction "A_A") (pintype "passive"))
      (node (ref "R13") (pin "2") (pinfunction "2_2") (pintype "passive"))
    )
    (net (code "45") (name "Net-(Q3-D)") (class "Default")
      (node (ref "Q3") (pin "3") (pinfunction "D_3") (pintype "passive"))
      (node (ref "X2") (pin "2") (pinfunction "KL_2") (pintype "passive"))
    )
    (net (code "46") (name "Net-(Q4-D)") (class "Default")
      (node (ref "Q4") (pin "3") (pinfunction "D_3") (pintype "passive"))
      (node (ref "X3") (pin "2") (pinfunction "KL_2") (pintype "passive"))
    )
    (net (code "47") (name "Net-(Q5-D)") (class "Default")
      (node (ref "Q5") (pin "3") (pinfunction "D_3") (pintype "passive"))
      (node (ref "X7") (pin "2") (pinfunction "KL_2") (pintype "passive"))
    )
    (net (code "48") (name "Net-(TP2-TP)") (class "Default")
      (node (ref "RFM12B") (pin "ANT") (pinfunction "ANT_ANT") (pintype "passive"))
      (node (ref "TP2") (pin "PP") (pinfunction "TP_PP") (pintype "input"))
    )
    (net (code "49") (name "unconnected-(IC2-PA4-Pad14)") (class "Default")
      (node (ref "IC2") (pin "14") (pinfunction "PA4_14") (pintype "bidirectional"))
    )
    (net (code "50") (name "unconnected-(IC2-PA8-Pad29)") (class "Default")
      (node (ref "IC2") (pin "29") (pinfunction "PA8_29") (pintype "bidirectional"))
    )
    (net (code "51") (name "unconnected-(IC2-PA15-Pad38)") (class "Default")
      (node (ref "IC2") (pin "38") (pinfunction "PA15_38") (pintype "bidirectional"))
    )
    (net (code "52") (name "unconnected-(IC2-PB3-Pad39)") (class "Default")
      (node (ref "IC2") (pin "39") (pinfunction "PB3_39") (pintype "bidirectional"))
    )
    (net (code "53") (name "unconnected-(IC2-PB5-Pad41)") (class "Default")
      (node (ref "IC2") (pin "41") (pinfunction "PB5_41") (pintype "bidirectional"))
    )
    (net (code "54") (name "unconnected-(IC2-PC0-Pad1)") (class "Default")
      (node (ref "IC2") (pin "1") (pinfunction "PC0_1") (pintype "bidirectional"))
    )
    (net (code "55") (name "unconnected-(IC2-PC13-Pad2)") (class "Default")
      (node (ref "IC2") (pin "2") (pinfunction "PC13_2") (pintype "bidirectional"))
    )
    (net (code "56") (name "unconnected-(IC5-PadDTR)") (class "Default")
      (node (ref "IC5") (pin "DTR") (pinfunction "DTR_DTR") (pintype "bidirectional"))
    )
    (net (code "57") (name "unconnected-(IC5-PadMIC+)") (class "Default")
      (node (ref "IC5") (pin "MIC+") (pinfunction "MIC+_MIC+") (pintype "bidirectional"))
    )
    (net (code "58") (name "unconnected-(IC5-PadMIC-)") (class "Default")
      (node (ref "IC5") (pin "MIC-") (pinfunction "MIC-_MIC-") (pintype "bidirectional"))
    )
    (net (code "59") (name "unconnected-(IC5-PadNET)") (class "Default")
      (node (ref "IC5") (pin "NET") (pinfunction "NET_NET") (pintype "bidirectional"))
    )
    (net (code "60") (name "unconnected-(IC5-PadRING)") (class "Default")
      (node (ref "IC5") (pin "RING") (pinfunction "RING_RING") (pintype "bidirectional"))
    )
    (net (code "61") (name "unconnected-(IC5-PadRST)") (class "Default")
      (node (ref "IC5") (pin "RST") (pinfunction "RST_RST") (pintype "bidirectional"))
    )
    (net (code "62") (name "unconnected-(IC5-PadSPK+)") (class "Default")
      (node (ref "IC5") (pin "SPK+") (pinfunction "SPK+_SPK+") (pintype "bidirectional"))
    )
    (net (code "63") (name "unconnected-(IC5-PadSPK-)") (class "Default")
      (node (ref "IC5") (pin "SPK-") (pinfunction "SPK-_SPK-") (pintype "bidirectional"))
    )
    (net (code "64") (name "unconnected-(JP2-Pad6)") (class "Default")
      (node (ref "JP2") (pin "6") (pinfunction "6_6") (pintype "passive"))
    )
    (net (code "65") (name "unconnected-(RFM12B-PadFFS)") (class "Default")
      (node (ref "RFM12B") (pin "FFS") (pinfunction "FFS_FFS") (pintype "bidirectional"))
    )
  )
)
